# Menu-display_schematic_2021-06-02.net
KiCad netlist of a schematic drawn in Altium Designer
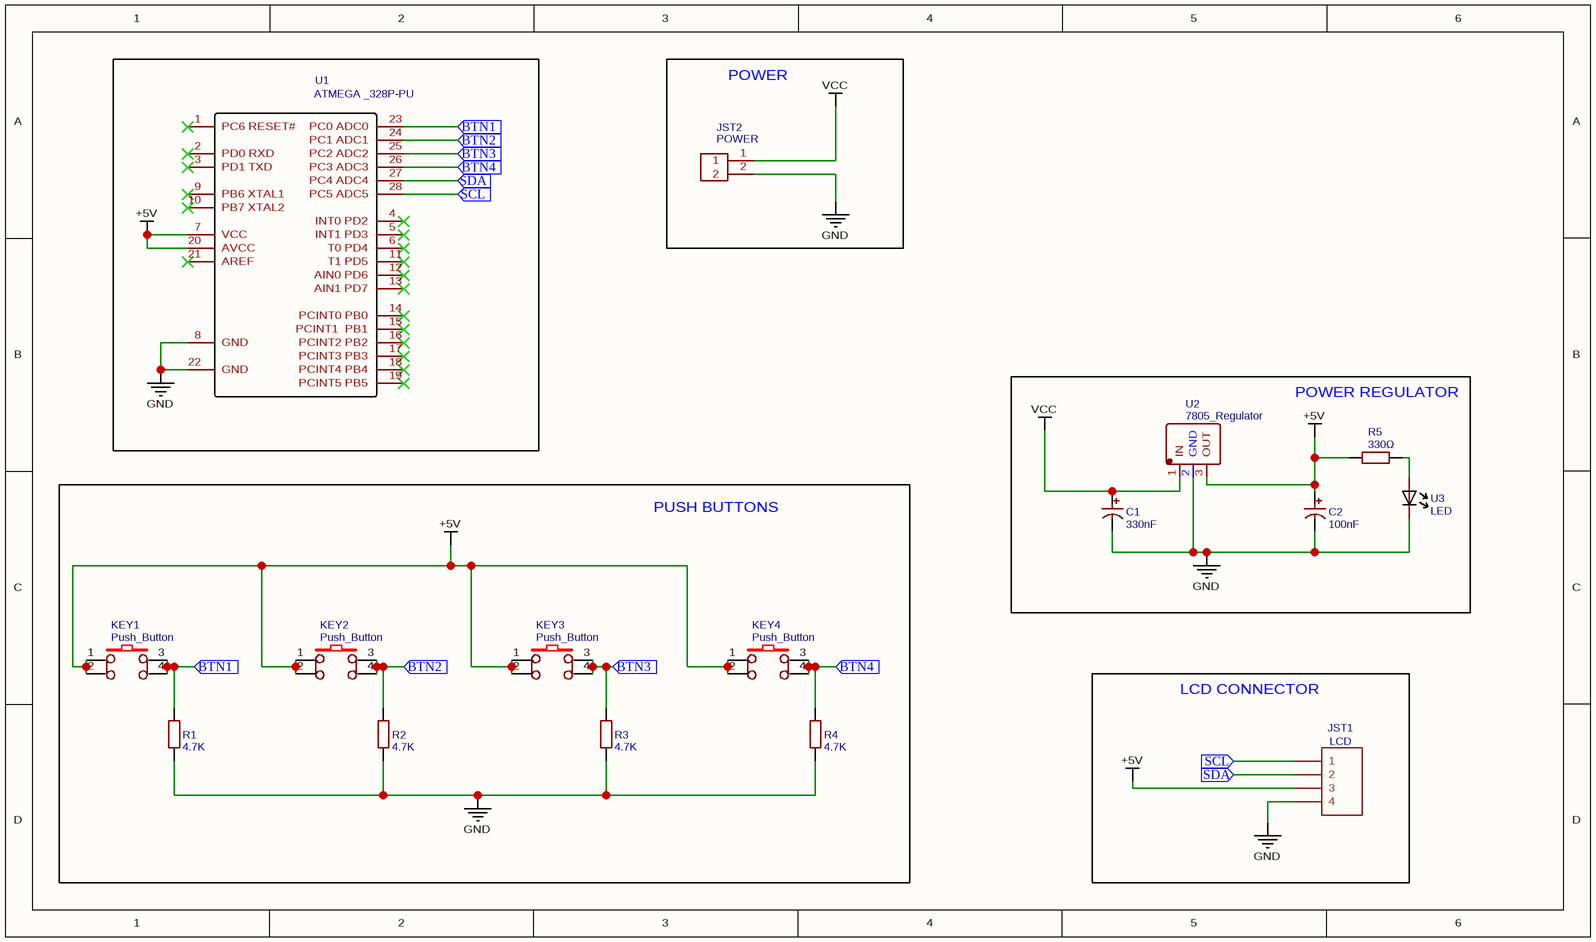
[diagram p0: Menu-display schematic_2021-06-02.schdoc]

(export (version "E")
  (design (tool "Eeschema 10.0.6"))
  (components
    (comp (ref "C1")
      (value "330nF")
      (fields (field (name "BOM_MANUFACTURER PART") "0.1UF 50V") (field (name "BOM_SUPPLIER PART") "C28061"))
      (libsource (lib "altium-import") (part "root_0_330nF_"))
    )
    (comp (ref "C2")
      (value "100nF")
      (fields (field (name "BOM_MANUFACTURER PART") "0.1UF 50V") (field (name "BOM_SUPPLIER PART") "C28061"))
      (libsource (lib "altium-import") (part "root_0_100nF_"))
    )
    (comp (ref "JST1")
      (value "LCD")
      (fields (field (name "CONTRIBUTOR") "fabiano.riccardi"))
      (libsource (lib "altium-import") (part "root_0_LCD_"))
    )
    (comp (ref "JST2")
      (value "POWER")
      (fields
        (field (name "BOM_MANUFACTURER PART") "XHB-2A Connector")
        (field (name "BOM_SUPPLIER PART") "C57981")
      )
      (libsource (lib "altium-import") (part "root_0_POWER_"))
    )
    (comp (ref "KEY1")
      (value "Push_Button")
      (fields
        (field (name "BOM_SUPPLIER PART") "C59980")
        (field (name "BOM_MANUFACTURER PART") "button6*6*8.5")
      )
      (libsource (lib "altium-import") (part "root_0_Push_Button_"))
    )
    (comp (ref "KEY2")
      (value "Push_Button")
      (fields
        (field (name "BOM_SUPPLIER PART") "C59980")
        (field (name "BOM_MANUFACTURER PART") "button6*6*8.5")
      )
      (libsource (lib "altium-import") (part "root_0_Push_Button_"))
    )
    (comp (ref "KEY3")
      (value "Push_Button")
      (fields
        (field (name "BOM_SUPPLIER PART") "C59980")
        (field (name "BOM_MANUFACTURER PART") "button6*6*8.5")
      )
      (libsource (lib "altium-import") (part "root_0_Push_Button_"))
    )
    (comp (ref "KEY4")
      (value "Push_Button")
      (fields
        (field (name "BOM_SUPPLIER PART") "C59980")
        (field (name "BOM_MANUFACTURER PART") "button6*6*8.5")
      )
      (libsource (lib "altium-import") (part "root_0_Push_Button_"))
    )
    (comp (ref "R1")
      (value "4.7K")
      (fields
        (field (name "POWER") "1/4W")
        (field (name "TOLERANCE") "±1%")
        (field (name "BOM_SUPPLIER PART") "E57439")
      )
      (libsource (lib "altium-import") (part "root_1_4.7K_"))
    )
    (comp (ref "R2")
      (value "4.7K")
      (fields
        (field (name "POWER") "1/4W")
        (field (name "TOLERANCE") "±1%")
        (field (name "BOM_SUPPLIER PART") "E57439")
      )
      (libsource (lib "altium-import") (part "root_1_4.7K_"))
    )
    (comp (ref "R3")
      (value "4.7K")
      (fields
        (field (name "POWER") "1/4W")
        (field (name "TOLERANCE") "±1%")
        (field (name "BOM_SUPPLIER PART") "E57439")
      )
      (libsource (lib "altium-import") (part "root_1_4.7K_"))
    )
    (comp (ref "R4")
      (value "4.7K")
      (fields
        (field (name "POWER") "1/4W")
        (field (name "TOLERANCE") "±1%")
        (field (name "BOM_SUPPLIER PART") "E57439")
      )
      (libsource (lib "altium-import") (part "root_1_4.7K_"))
    )
    (comp (ref "R5")
      (value "330Ω")
      (fields
        (field (name "POWER") "1/4W")
        (field (name "TOLERANCE") "±1%")
        (field (name "BOM_SUPPLIER PART") "E57439")
      )
      (libsource (lib "altium-import") (part "root_0_330Ω_"))
    )
    (comp (ref "U1")
      (value "ATMEGA _328P-PU")
      (fields
        (field (name "BOM_MANUFACTURER PART") "ATMEGA328P-PU")
        (field (name "BOM_SUPPLIER PART") "C33901")
        (field (name "CONTRIBUTOR") "LCSC")
      )
      (libsource (lib "altium-import") (part "root_0_ATMEGA _328P-PU_"))
    )
    (comp (ref "U2")
      (value "7805_Regulator")
      (fields
        (field (name "BOM_SUPPLIER PART") "C305416")
        (field (name "BOM_MANUFACTURER PART") "7805")
        (field (name "CONTRIBUTOR") "LCSC")
      )
      (libsource (lib "altium-import") (part "root_1_7805_Regulator_"))
    )
    (comp (ref "U3")
      (value "LED")
      (fields (field (name "BOM_MANUFACTURER PART") "5mm LED") (field (name "CONTRIBUTOR") "Axbri"))
      (libsource (lib "altium-import") (part "root_3_LED_"))
    )
  )
  (nets
    (net (code "1") (name "+5V") (class "Default")
      (node (ref "C2") (pin "1") (pinfunction "1_1") (pintype "passive"))
      (node (ref "JST1") (pin "3") (pinfunction "3_3") (pintype "passive"))
      (node (ref "KEY1") (pin "1") (pinfunction "1_1") (pintype "passive"))
      (node (ref "KEY1") (pin "2") (pinfunction "2_2") (pintype "passive"))
      (node (ref "KEY2") (pin "1") (pinfunction "1_1") (pintype "passive"))
      (node (ref "KEY2") (pin "2") (pinfunction "2_2") (pintype "passive"))
      (node (ref "KEY3") (pin "1") (pinfunction "1_1") (pintype "passive"))
      (node (ref "KEY3") (pin "2") (pinfunction "2_2") (pintype "passive"))
      (node (ref "KEY4") (pin "1") (pinfunction "1_1") (pintype "passive"))
      (node (ref "KEY4") (pin "2") (pinfunction "2_2") (pintype "passive"))
      (node (ref "R5") (pin "1") (pinfunction "1_1") (pintype "passive"))
      (node (ref "U1") (pin "20") (pinfunction "AVCC_20") (pintype "passive"))
      (node (ref "U1") (pin "7") (pinfunction "VCC_7") (pintype "passive"))
      (node (ref "U2") (pin "3") (pinfunction "OUT_3") (pintype "passive"))
    )
    (net (code "2") (name "/BTN1") (class "Default")
      (node (ref "KEY1") (pin "3") (pinfunction "3_3") (pintype "passive"))
      (node (ref "KEY1") (pin "4") (pinfunction "4_4") (pintype "passive"))
      (node (ref "R1") (pin "2") (pinfunction "2_2") (pintype "passive"))
      (node (ref "U1") (pin "23") (pinfunction "PC0_ADC0_23") (pintype "passive"))
    )
    (net (code "3") (name "/BTN2") (class "Default")
      (node (ref "KEY2") (pin "3") (pinfunction "3_3") (pintype "passive"))
      (node (ref "KEY2") (pin "4") (pinfunction "4_4") (pintype "passive"))
      (node (ref "R2") (pin "2") (pinfunction "2_2") (pintype "passive"))
      (node (ref "U1") (pin "24") (pinfunction "PC1_ADC1_24") (pintype "passive"))
    )
    (net (code "4") (name "/BTN3") (class "Default")
      (node (ref "KEY3") (pin "3") (pinfunction "3_3") (pintype "passive"))
      (node (ref "KEY3") (pin "4") (pinfunction "4_4") (pintype "passive"))
      (node (ref "R3") (pin "2") (pinfunction "2_2") (pintype "passive"))
      (node (ref "U1") (pin "25") (pinfunction "PC2_ADC2_25") (pintype "passive"))
    )
    (net (code "5") (name "/BTN4") (class "Default")
      (node (ref "KEY4") (pin "3") (pinfunction "3_3") (pintype "passive"))
      (node (ref "KEY4") (pin "4") (pinfunction "4_4") (pintype "passive"))
      (node (ref "R4") (pin "2") (pinfunction "2_2") (pintype "passive"))
      (node (ref "U1") (pin "26") (pinfunction "PC3_ADC3_26") (pintype "passive"))
    )
    (net (code "6") (name "/SCL") (class "Default")
      (node (ref "JST1") (pin "1") (pinfunction "1_1") (pintype "passive"))
      (node (ref "U1") (pin "28") (pinfunction "PC5_ADC5_28") (pintype "passive"))
    )
    (net (code "7") (name "/SDA") (class "Default")
      (node (ref "JST1") (pin "2") (pinfunction "2_2") (pintype "passive"))
      (node (ref "U1") (pin "27") (pinfunction "PC4_ADC4_27") (pintype "passive"))
    )
    (net (code "8") (name "GND") (class "Default")
      (node (ref "C1") (pin "2") (pinfunction "2_2") (pintype "passive"))
      (node (ref "C2") (pin "2") (pinfunction "2_2") (pintype "passive"))
      (node (ref "JST1") (pin "4") (pinfunction "4_4") (pintype "passive"))
      (node (ref "JST2") (pin "2") (pinfunction "2_2") (pintype "passive"))
      (node (ref "R1") (pin "1") (pinfunction "1_1") (pintype "passive"))
      (node (ref "R2") (pin "1") (pinfunction "1_1") (pintype "passive"))
      (node (ref "R3") (pin "1") (pinfunction "1_1") (pintype "passive"))
      (node (ref "R4") (pin "1") (pinfunction "1_1") (pintype "passive"))
      (node (ref "U1") (pin "22") (pinfunction "GND_22") (pintype "passive"))
      (node (ref "U1") (pin "8") (pinfunction "GND_8") (pintype "passive"))
      (node (ref "U2") (pin "2") (pinfunction "GND_2") (pintype "passive"))
      (node (ref "U3") (pin "2") (pinfunction "2_2") (pintype "passive"))
    )
    (net (code "9") (name "Net-(R5-Pad2)") (class "Default")
      (node (ref "R5") (pin "2") (pinfunction "2_2") (pintype "passive"))
      (node (ref "U3") (pin "1") (pinfunction "1_1") (pintype "passive"))
    )
    (net (code "10") (name "VCC") (class "Default")
      (node (ref "C1") (pin "1") (pinfunction "1_1") (pintype "passive"))
      (node (ref "JST2") (pin "1") (pinfunction "1_1") (pintype "passive"))
      (node (ref "U2") (pin "1") (pinfunction "IN_1") (pintype "passive"))
    )
    (net (code "11") (name "unconnected-(U1-AIN0_PD6-Pad12)") (class "Default")
      (node (ref "U1") (pin "12") (pinfunction "AIN0_PD6_12") (pintype "passive+no_connect"))
    )
    (net (code "12") (name "unconnected-(U1-AIN1_PD7-Pad13)") (class "Default")
      (node (ref "U1") (pin "13") (pinfunction "AIN1_PD7_13") (pintype "passive+no_connect"))
    )
    (net (code "13") (name "unconnected-(U1-AREF-Pad21)") (class "Default")
      (node (ref "U1") (pin "21") (pinfunction "AREF_21") (pintype "passive+no_connect"))
    )
    (net (code "14") (name "unconnected-(U1-INT0_PD2-Pad4)") (class "Default")
      (node (ref "U1") (pin "4") (pinfunction "INT0_PD2_4") (pintype "passive+no_connect"))
    )
    (net (code "15") (name "unconnected-(U1-INT1_PD3-Pad5)") (class "Default")
      (node (ref "U1") (pin "5") (pinfunction "INT1_PD3_5") (pintype "passive+no_connect"))
    )
    (net (code "16") (name "unconnected-(U1-PB6_XTAL1-Pad9)") (class "Default")
      (node (ref "U1") (pin "9") (pinfunction "PB6_XTAL1_9") (pintype "passive+no_connect"))
    )
    (net (code "17") (name "unconnected-(U1-PB7_XTAL2-Pad10)") (class "Default")
      (node (ref "U1") (pin "10") (pinfunction "PB7_XTAL2_10") (pintype "passive+no_connect"))
    )
    (net (code "18") (name "unconnected-(U1-PC6_RESET#-Pad1)") (class "Default")
      (node (ref "U1") (pin "1") (pinfunction "PC6_RESET#_1") (pintype "passive+no_connect"))
    )
    (net (code "19") (name "unconnected-(U1-PCINT0_PB0-Pad14)") (class "Default")
      (node (ref "U1") (pin "14") (pinfunction "PCINT0_PB0_14") (pintype "passive+no_connect"))
    )
    (net (code "20") (name "unconnected-(U1-PCINT1__PB1-Pad15)") (class "Default")
      (node (ref "U1") (pin "15") (pinfunction "PCINT1__PB1_15") (pintype "passive+no_connect"))
    )
    (net (code "21") (name "unconnected-(U1-PCINT2_PB2-Pad16)") (class "Default")
      (node (ref "U1") (pin "16") (pinfunction "PCINT2_PB2_16") (pintype "passive+no_connect"))
    )
    (net (code "22") (name "unconnected-(U1-PCINT3_PB3-Pad17)") (class "Default")
      (node (ref "U1") (pin "17") (pinfunction "PCINT3_PB3_17") (pintype "passive+no_connect"))
    )
    (net (code "23") (name "unconnected-(U1-PCINT4_PB4-Pad18)") (class "Default")
      (node (ref "U1") (pin "18") (pinfunction "PCINT4_PB4_18") (pintype "passive+no_connect"))
    )
    (net (code "24") (name "unconnected-(U1-PCINT5_PB5-Pad19)") (class "Default")
      (node (ref "U1") (pin "19") (pinfunction "PCINT5_PB5_19") (pintype "passive+no_connect"))
    )
    (net (code "25") (name "unconnected-(U1-PD0_RXD-Pad2)") (class "Default")
      (node (ref "U1") (pin "2") (pinfunction "PD0_RXD_2") (pintype "passive+no_connect"))
    )
    (net (code "26") (name "unconnected-(U1-PD1_TXD-Pad3)") (class "Default")
      (node (ref "U1") (pin "3") (pinfunction "PD1_TXD_3") (pintype "passive+no_connect"))
    )
    (net (code "27") (name "unconnected-(U1-T0_PD4-Pad6)") (class "Default")
      (node (ref "U1") (pin "6") (pinfunction "T0_PD4_6") (pintype "passive+no_connect"))
    )
    (net (code "28") (name "unconnected-(U1-T1_PD5-Pad11)") (class "Default")
      (node (ref "U1") (pin "11") (pinfunction "T1_PD5_11") (pintype "passive+no_connect"))
    )
  )
)
